# NodeNadelAdapterLayer1.net
KiCad netlist of a schematic drawn in EAGLE
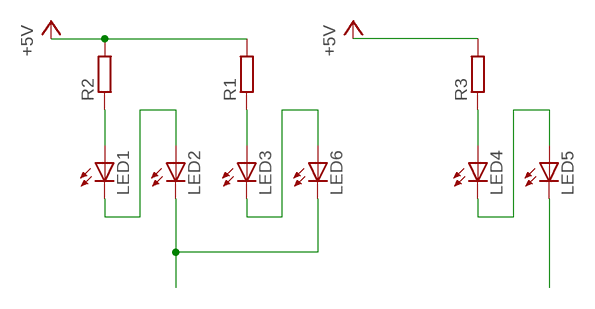
[diagram p0: schematic, sheet 1]

(export (version "E")
  (design (tool "Eeschema 10.0.6"))
  (components
    (comp (ref "LED1")
      (value "LEDSML0805")
      (footprint "eagle-import:SML0805")
      (libsource (lib "eagle-import") (part "LEDSML0805"))
    )
    (comp (ref "LED2")
      (value "LEDSML0805")
      (footprint "eagle-import:SML0805")
      (libsource (lib "eagle-import") (part "LEDSML0805"))
    )
    (comp (ref "LED3")
      (value "LEDSML0805")
      (footprint "eagle-import:SML0805")
      (libsource (lib "eagle-import") (part "LEDSML0805"))
    )
    (comp (ref "LED4")
      (value "LEDSML0805")
      (footprint "eagle-import:SML0805")
      (libsource (lib "eagle-import") (part "LEDSML0805"))
    )
    (comp (ref "LED5")
      (value "LEDSML0805")
      (footprint "eagle-import:SML0805")
      (libsource (lib "eagle-import") (part "LEDSML0805"))
    )
    (comp (ref "LED6")
      (value "LEDSML0805")
      (footprint "eagle-import:SML0805")
      (libsource (lib "eagle-import") (part "LEDSML0805"))
    )
    (comp (ref "R1")
      (value "R-EU_R0603")
      (footprint "eagle-import:R0603")
      (libsource (lib "eagle-import") (part "R-EU_R0603"))
    )
    (comp (ref "R2")
      (value "R-EU_R0603")
      (footprint "eagle-import:R0603")
      (libsource (lib "eagle-import") (part "R-EU_R0603"))
    )
    (comp (ref "R3")
      (value "R-EU_R0603")
      (footprint "eagle-import:R0603")
      (libsource (lib "eagle-import") (part "R-EU_R0603"))
    )
  )
  (nets
    (net (code "1") (name "+5V") (class "Default")
      (node (ref "R1") (pin "2") (pinfunction "2_2") (pintype "passive"))
      (node (ref "R2") (pin "2") (pinfunction "2_2") (pintype "passive"))
      (node (ref "R3") (pin "2") (pinfunction "2_2") (pintype "passive"))
    )
    (net (code "2") (name "Net-(LED1-PadA)") (class "Default")
      (node (ref "LED1") (pin "A") (pinfunction "A_A") (pintype "passive"))
      (node (ref "R2") (pin "1") (pinfunction "1_1") (pintype "passive"))
    )
    (net (code "3") (name "Net-(LED1-PadC)") (class "Default")
      (node (ref "LED1") (pin "C") (pinfunction "C_C") (pintype "passive"))
      (node (ref "LED2") (pin "A") (pinfunction "A_A") (pintype "passive"))
    )
    (net (code "4") (name "Net-(LED2-PadC)") (class "Default")
      (node (ref "LED2") (pin "C") (pinfunction "C_C") (pintype "passive"))
      (node (ref "LED6") (pin "C") (pinfunction "C_C") (pintype "passive"))
    )
    (net (code "5") (name "Net-(LED3-PadA)") (class "Default")
      (node (ref "LED3") (pin "A") (pinfunction "A_A") (pintype "passive"))
      (node (ref "R1") (pin "1") (pinfunction "1_1") (pintype "passive"))
    )
    (net (code "6") (name "Net-(LED3-PadC)") (class "Default")
      (node (ref "LED3") (pin "C") (pinfunction "C_C") (pintype "passive"))
      (node (ref "LED6") (pin "A") (pinfunction "A_A") (pintype "passive"))
    )
    (net (code "7") (name "Net-(LED4-PadA)") (class "Default")
      (node (ref "LED4") (pin "A") (pinfunction "A_A") (pintype "passive"))
      (node (ref "R3") (pin "1") (pinfunction "1_1") (pintype "passive"))
    )
    (net (code "8") (name "Net-(LED4-PadC)") (class "Default")
      (node (ref "LED4") (pin "C") (pinfunction "C_C") (pintype "passive"))
      (node (ref "LED5") (pin "A") (pinfunction "A_A") (pintype "passive"))
    )
    (net (code "9") (name "unconnected-(LED5-PadC)") (class "Default")
      (node (ref "LED5") (pin "C") (pinfunction "C_C") (pintype "passive"))
    )
  )
)
